# Wireless_Buzzer.net
KiCad netlist of a schematic drawn in EAGLE
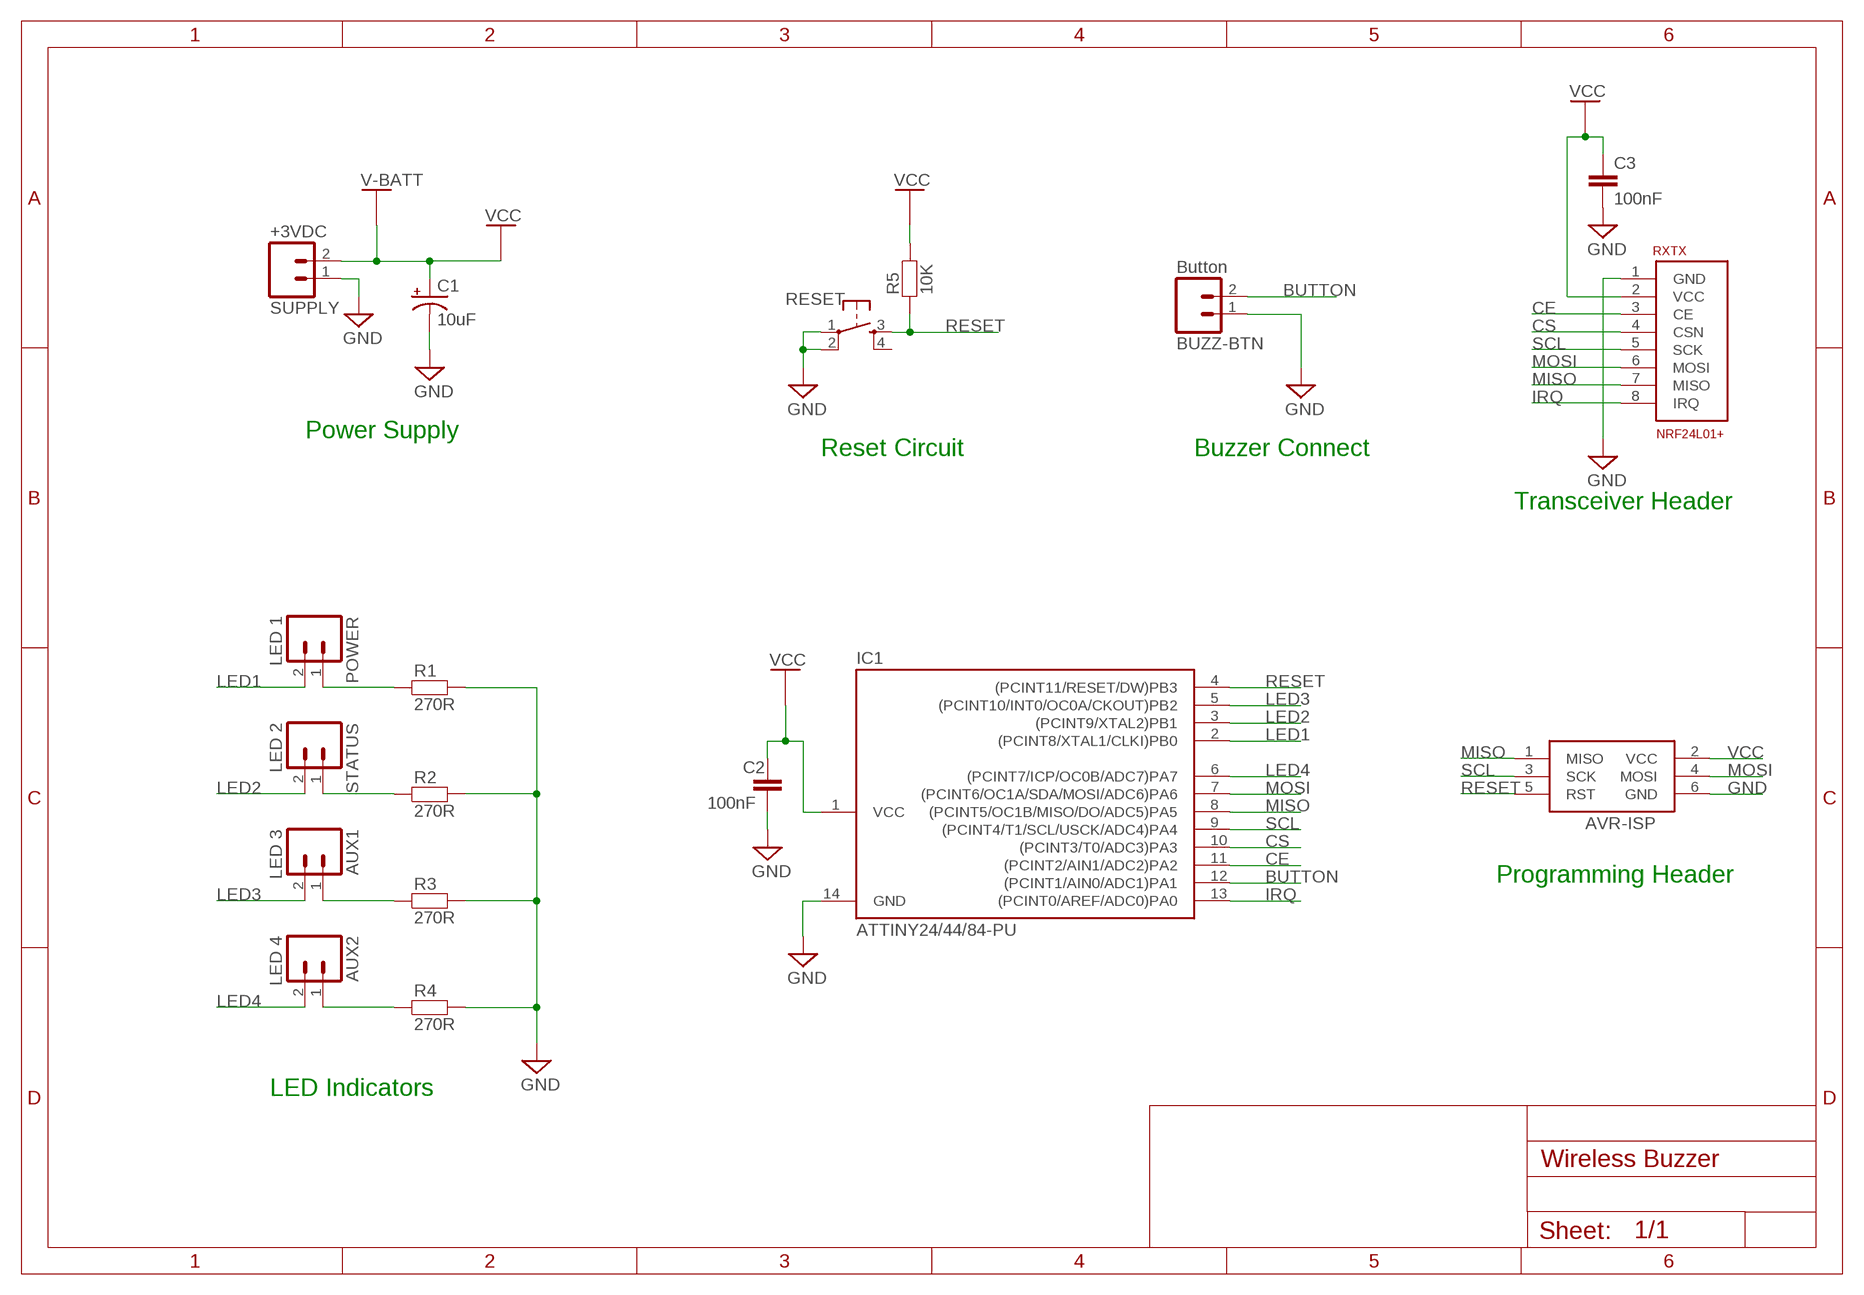
[diagram p0: schematic, sheet 1]

(export (version "E")
  (design (tool "Eeschema 10.0.6"))
  (components
    (comp (ref "AUX1")
      (value "LED 3")
      (footprint "eagle-import:KK-CONNECT-2WAY-PG")
      (libsource (lib "eagle-import") (part "KK-CONNECT-2WAY_PG"))
    )
    (comp (ref "AUX2")
      (value "LED 4")
      (footprint "eagle-import:KK-CONNECT-2WAY-PG")
      (libsource (lib "eagle-import") (part "KK-CONNECT-2WAY_PG"))
    )
    (comp (ref "AVR-ISP")
      (value "AVRISP-6")
      (footprint "eagle-import:AVRISP")
      (libsource (lib "eagle-import") (part "AVRISP-6"))
    )
    (comp (ref "BUZZ-BTN")
      (value "Button")
      (footprint "eagle-import:KK-CONNECT-2WAY-PG")
      (libsource (lib "eagle-import") (part "KK-CONNECT-2WAY_PG"))
    )
    (comp (ref "C1")
      (value "10uF")
      (footprint "eagle-import:SM-TANT-D_EIA7343")
      (libsource (lib "eagle-import") (part "CAP-POL-SM-TANT_D"))
    )
    (comp (ref "C2")
      (value "100nF")
      (footprint "eagle-import:SM-1206_PG")
      (libsource (lib "eagle-import") (part "CAPACITOR-SM-1206"))
    )
    (comp (ref "C3")
      (value "100nF")
      (footprint "eagle-import:SM-1206_PG")
      (libsource (lib "eagle-import") (part "CAPACITOR-SM-1206"))
    )
    (comp (ref "IC1")
      (value "ATTINY24/44/84-PU")
      (footprint "eagle-import:DIL14")
      (libsource (lib "eagle-import") (part "ATTINY24/44/84-PU"))
    )
    (comp (ref "POWER")
      (value "LED 1")
      (footprint "eagle-import:KK-CONNECT-2WAY-PG")
      (libsource (lib "eagle-import") (part "KK-CONNECT-2WAY_PG"))
    )
    (comp (ref "R1")
      (value "270R")
      (footprint "eagle-import:SM-1206_PG")
      (libsource (lib "eagle-import") (part "RESISTOR-SM-1206"))
    )
    (comp (ref "R2")
      (value "270R")
      (footprint "eagle-import:SM-1206_PG")
      (libsource (lib "eagle-import") (part "RESISTOR-SM-1206"))
    )
    (comp (ref "R3")
      (value "270R")
      (footprint "eagle-import:SM-1206_PG")
      (libsource (lib "eagle-import") (part "RESISTOR-SM-1206"))
    )
    (comp (ref "R4")
      (value "270R")
      (footprint "eagle-import:SM-1206_PG")
      (libsource (lib "eagle-import") (part "RESISTOR-SM-1206"))
    )
    (comp (ref "R5")
      (value "10K")
      (footprint "eagle-import:SM-1206_PG")
      (libsource (lib "eagle-import") (part "RESISTOR-SM-1206"))
    )
    (comp (ref "RESET")
      (value "DTSM-6")
      (footprint "eagle-import:DTSM-6")
      (libsource (lib "eagle-import") (part "DTSM-6"))
    )
    (comp (ref "RXTX")
      (value "NRF24L01+")
      (footprint "eagle-import:NRF24L01+-HEADER")
      (libsource (lib "eagle-import") (part "NRF24L01+"))
    )
    (comp (ref "STATUS")
      (value "LED 2")
      (footprint "eagle-import:KK-CONNECT-2WAY-PG")
      (libsource (lib "eagle-import") (part "KK-CONNECT-2WAY_PG"))
    )
    (comp (ref "SUPPLY")
      (value "+3VDC")
      (footprint "eagle-import:KK-CONNECT-2WAY-PG")
      (libsource (lib "eagle-import") (part "KK-CONNECT-2WAY_PG"))
    )
  )
  (nets
    (net (code "1") (name "/BUTTON") (class "Default")
      (node (ref "BUZZ-BTN") (pin "2") (pinfunction "2_2") (pintype "passive"))
      (node (ref "IC1") (pin "12") (pinfunction "(PCINT1/AIN0/ADC1)PA1_12") (pintype "bidirectional"))
    )
    (net (code "2") (name "/CE") (class "Default")
      (node (ref "IC1") (pin "11") (pinfunction "(PCINT2/AIN1/ADC2)PA2_11") (pintype "bidirectional"))
      (node (ref "RXTX") (pin "3") (pinfunction "CE_3") (pintype "bidirectional"))
    )
    (net (code "3") (name "/CS") (class "Default")
      (node (ref "IC1") (pin "10") (pinfunction "(PCINT3/T0/ADC3)PA3_10") (pintype "bidirectional"))
      (node (ref "RXTX") (pin "4") (pinfunction "CSN_4") (pintype "bidirectional"))
    )
    (net (code "4") (name "/IRQ") (class "Default")
      (node (ref "IC1") (pin "13") (pinfunction "(PCINT0/AREF/ADC0)PA0_13") (pintype "bidirectional"))
      (node (ref "RXTX") (pin "8") (pinfunction "IRQ_8") (pintype "bidirectional"))
    )
    (net (code "5") (name "/LED1") (class "Default")
      (node (ref "IC1") (pin "2") (pinfunction "(PCINT8/XTAL1/CLKI)PB0_2") (pintype "bidirectional"))
      (node (ref "POWER") (pin "2") (pinfunction "2_2") (pintype "passive"))
    )
    (net (code "6") (name "/LED2") (class "Default")
      (node (ref "IC1") (pin "3") (pinfunction "(PCINT9/XTAL2)PB1_3") (pintype "bidirectional"))
      (node (ref "STATUS") (pin "2") (pinfunction "2_2") (pintype "passive"))
    )
    (net (code "7") (name "/LED3") (class "Default")
      (node (ref "AUX1") (pin "2") (pinfunction "2_2") (pintype "passive"))
      (node (ref "IC1") (pin "5") (pinfunction "(PCINT10/INT0/OC0A/CKOUT)PB2_5") (pintype "bidirectional"))
    )
    (net (code "8") (name "/LED4") (class "Default")
      (node (ref "AUX2") (pin "2") (pinfunction "2_2") (pintype "passive"))
      (node (ref "IC1") (pin "6") (pinfunction "(PCINT7/ICP/OC0B/ADC7)PA7_6") (pintype "bidirectional"))
    )
    (net (code "9") (name "/MISO") (class "Default")
      (node (ref "AVR-ISP") (pin "1") (pinfunction "MISO_1") (pintype "input"))
      (node (ref "IC1") (pin "8") (pinfunction "(PCINT5/OC1B/MISO/DO/ADC5)PA5_8") (pintype "bidirectional"))
      (node (ref "RXTX") (pin "7") (pinfunction "MISO_7") (pintype "bidirectional"))
    )
    (net (code "10") (name "/MOSI") (class "Default")
      (node (ref "AVR-ISP") (pin "4") (pinfunction "MOSI_4") (pintype "output"))
      (node (ref "IC1") (pin "7") (pinfunction "(PCINT6/OC1A/SDA/MOSI/ADC6)PA6_7") (pintype "bidirectional"))
      (node (ref "RXTX") (pin "6") (pinfunction "MOSI_6") (pintype "bidirectional"))
    )
    (net (code "11") (name "/RESET") (class "Default")
      (node (ref "AVR-ISP") (pin "5") (pinfunction "RST_5") (pintype "output"))
      (node (ref "IC1") (pin "4") (pinfunction "(PCINT11/RESET/DW)PB3_4") (pintype "bidirectional"))
      (node (ref "R5") (pin "P$1") (pinfunction "1_P$1") (pintype "passive"))
      (node (ref "RESET") (pin "3") (pinfunction "3_3") (pintype "passive"))
    )
    (net (code "12") (name "/SCL") (class "Default")
      (node (ref "AVR-ISP") (pin "3") (pinfunction "SCK_3") (pintype "output"))
      (node (ref "IC1") (pin "9") (pinfunction "(PCINT4/T1/SCL/USCK/ADC4)PA4_9") (pintype "bidirectional"))
      (node (ref "RXTX") (pin "5") (pinfunction "SCK_5") (pintype "bidirectional"))
    )
    (net (code "13") (name "GND") (class "Default")
      (node (ref "AVR-ISP") (pin "6") (pinfunction "GND_6") (pintype "power_in"))
      (node (ref "BUZZ-BTN") (pin "1") (pinfunction "1_1") (pintype "passive"))
      (node (ref "C1") (pin "C") (pinfunction "-_C") (pintype "passive"))
      (node (ref "C2") (pin "P$2") (pinfunction "2_P$2") (pintype "passive"))
      (node (ref "C3") (pin "P$2") (pinfunction "2_P$2") (pintype "passive"))
      (node (ref "IC1") (pin "14") (pinfunction "GND_14") (pintype "power_in"))
      (node (ref "R1") (pin "P$2") (pinfunction "2_P$2") (pintype "passive"))
      (node (ref "R2") (pin "P$2") (pinfunction "2_P$2") (pintype "passive"))
      (node (ref "R3") (pin "P$2") (pinfunction "2_P$2") (pintype "passive"))
      (node (ref "R4") (pin "P$2") (pinfunction "2_P$2") (pintype "passive"))
      (node (ref "RESET") (pin "1") (pinfunction "1_1") (pintype "passive"))
      (node (ref "RESET") (pin "2") (pinfunction "2_2") (pintype "passive"))
      (node (ref "RXTX") (pin "1") (pinfunction "GND_1") (pintype "power_in"))
      (node (ref "SUPPLY") (pin "1") (pinfunction "1_1") (pintype "passive"))
    )
    (net (code "14") (name "Net-(R1-1)") (class "Default")
      (node (ref "POWER") (pin "1") (pinfunction "1_1") (pintype "passive"))
      (node (ref "R1") (pin "P$1") (pinfunction "1_P$1") (pintype "passive"))
    )
    (net (code "15") (name "Net-(R2-1)") (class "Default")
      (node (ref "R2") (pin "P$1") (pinfunction "1_P$1") (pintype "passive"))
      (node (ref "STATUS") (pin "1") (pinfunction "1_1") (pintype "passive"))
    )
    (net (code "16") (name "Net-(R3-1)") (class "Default")
      (node (ref "AUX1") (pin "1") (pinfunction "1_1") (pintype "passive"))
      (node (ref "R3") (pin "P$1") (pinfunction "1_P$1") (pintype "passive"))
    )
    (net (code "17") (name "Net-(R4-1)") (class "Default")
      (node (ref "AUX2") (pin "1") (pinfunction "1_1") (pintype "passive"))
      (node (ref "R4") (pin "P$1") (pinfunction "1_P$1") (pintype "passive"))
    )
    (net (code "18") (name "V-BATT") (class "Default")
      (node (ref "AVR-ISP") (pin "2") (pinfunction "VCC_2") (pintype "power_in"))
      (node (ref "C1") (pin "A") (pinfunction "+_A") (pintype "passive"))
      (node (ref "C2") (pin "P$1") (pinfunction "1_P$1") (pintype "passive"))
      (node (ref "C3") (pin "P$1") (pinfunction "1_P$1") (pintype "passive"))
      (node (ref "IC1") (pin "1") (pinfunction "VCC_1") (pintype "power_in"))
      (node (ref "R5") (pin "P$2") (pinfunction "2_P$2") (pintype "passive"))
      (node (ref "RXTX") (pin "2") (pinfunction "VCC_2") (pintype "power_in"))
      (node (ref "SUPPLY") (pin "2") (pinfunction "2_2") (pintype "passive"))
    )
    (net (code "19") (name "unconnected-(RESET-Pad4)") (class "Default")
      (node (ref "RESET") (pin "4") (pinfunction "4_4") (pintype "passive"))
    )
  )
)
